# FOTA_MicroController.net
KiCad netlist of a schematic drawn in Altium Designer
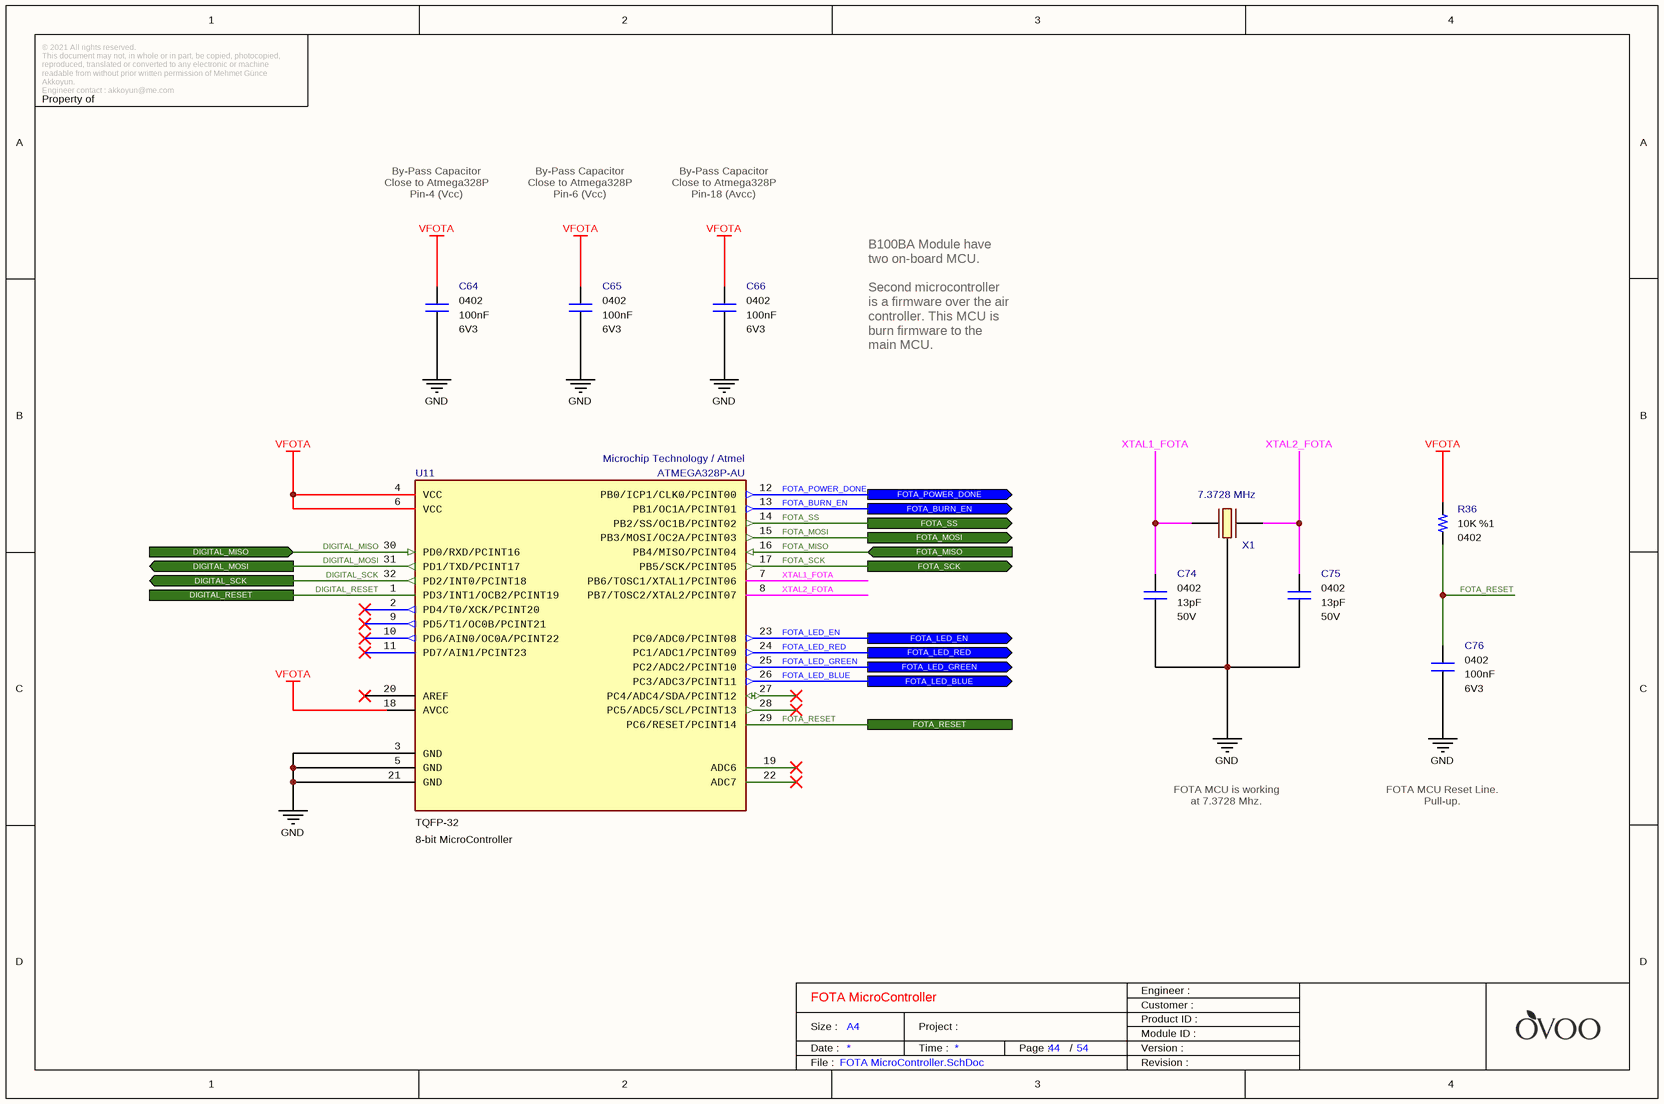
[diagram p0: FOTA MicroController.SchDoc]

(export (version "E")
  (design (tool "Eeschema 10.0.6"))
  (components
    (comp (ref "C64")
      (value "100nF")
      (footprint "CAPACITOR_0402")
      (description "Capacitor - 100nF [0402-6V3] (Ceramic)")
      (fields
        (field (name "TOLERANCE") "%10")
        (field (name "CASE") "0402")
        (field (name "VOLTAGE") "6V3")
        (field (name "MANUFACTURER PART NUMBER") "04026D104KAT4A")
      )
      (libsource (lib "Ovoo_Library") (part "Capacitor - 100nF [0402-6V3]"))
    )
    (comp (ref "C65")
      (value "100nF")
      (footprint "CAPACITOR_0402")
      (description "Capacitor - 100nF [0402-6V3] (Ceramic)")
      (fields
        (field (name "TOLERANCE") "%10")
        (field (name "CASE") "0402")
        (field (name "VOLTAGE") "6V3")
        (field (name "MANUFACTURER PART NUMBER") "04026D104KAT4A")
      )
      (libsource (lib "Ovoo_Library") (part "Capacitor - 100nF [0402-6V3]"))
    )
    (comp (ref "C66")
      (value "100nF")
      (footprint "CAPACITOR_0402")
      (description "Capacitor - 100nF [0402-6V3] (Ceramic)")
      (fields
        (field (name "TOLERANCE") "%10")
        (field (name "CASE") "0402")
        (field (name "VOLTAGE") "6V3")
        (field (name "MANUFACTURER PART NUMBER") "04026D104KAT4A")
      )
      (libsource (lib "Ovoo_Library") (part "Capacitor - 100nF [0402-6V3]"))
    )
    (comp (ref "C74")
      (value "13pF")
      (footprint "CAPACITOR_0402")
      (description "Capacitor - 13pF [0402] (Ceramic)")
      (fields
        (field (name "TOLERANCE") "1%")
        (field (name "VOLTAGE") "50V")
        (field (name "CASE") "0402")
        (field (name "MANUFACTURER PART NUMBER") "CBR04C130F5GAC")
      )
      (libsource (lib "Ovoo_Library") (part "Capacitor - 13pF [0402-50V]"))
    )
    (comp (ref "C75")
      (value "13pF")
      (footprint "CAPACITOR_0402")
      (description "Capacitor - 13pF [0402] (Ceramic)")
      (fields
        (field (name "TOLERANCE") "1%")
        (field (name "VOLTAGE") "50V")
        (field (name "CASE") "0402")
        (field (name "MANUFACTURER PART NUMBER") "CBR04C130F5GAC")
      )
      (libsource (lib "Ovoo_Library") (part "Capacitor - 13pF [0402-50V]"))
    )
    (comp (ref "C76")
      (value "100nF")
      (footprint "CAPACITOR_0402")
      (description "Capacitor - 100nF [0402-6V3] (Ceramic)")
      (fields
        (field (name "TOLERANCE") "%10")
        (field (name "CASE") "0402")
        (field (name "VOLTAGE") "6V3")
        (field (name "MANUFACTURER PART NUMBER") "04026D104KAT4A")
      )
      (libsource (lib "Ovoo_Library") (part "Capacitor - 100nF [0402-6V3]"))
    )
    (comp (ref "R36")
      (value "10K")
      (footprint "RESISTOR_0402")
      (description "Thick Film Resistors - SMD 1/16 W 10 Kohms 1%")
      (fields
        (field (name "TOLERANCE") "%1")
        (field (name "CASE") "0402")
        (field (name "MANUFACTURER PART NUMBER") "CRCW040210K0FKED")
        (field (name "MOUSER PART NUMBER") "71-CRCW0402-10K-E3")
      )
      (libsource (lib "Ovoo_Library") (part "Resistor - 10K"))
    )
    (comp (ref "U11")
      (value "8-bit MicroController")
      (footprint "TQFP32")
      (description "8-bit Microcontrollers - MCU 32KB In-system Flash 20MHz 1.8V-5.5V")
      (fields
        (field (name "CASE") "TQFP-32")
        (field (name "MOUSER PART NUMBER") "556-ATMEGA328P-AU")
        (field (name "MANUFACTURER PART NUMBER") "ATMEGA328P-AU")
        (field (name "MANUFACTURER NAME") "Microchip Technology / Atmel")
      )
      (libsource (lib "Ovoo_Library") (part "IC - ATMEGA328P"))
    )
    (comp (ref "X1")
      (value "7.3728 MHz")
      (footprint "ABRACON_CRYSTAL")
      (description "Crystals 7.3728MHz 18pF -40C +85C")
      (fields
        (field (name "TOLERANCE") "20 ppm")
        (field (name "MANUFACTURER PART NUMBER") "ABMM2-7.3728MHZ-E2-T")
      )
      (libsource (lib "Ovoo_Library") (part "Crystal - 7.3728 MHz (Abracon)"))
    )
  )
  (nets
    (net (code "1") (name "/DIGITAL_MISO") (class "Default")
      (node (ref "U11") (pin "30") (pinfunction "PD0/RXD/PCINT16_30") (pintype "input"))
    )
    (net (code "2") (name "/DIGITAL_MOSI") (class "Default")
      (node (ref "U11") (pin "31") (pinfunction "PD1/TXD/PCINT17_31") (pintype "output"))
    )
    (net (code "3") (name "/DIGITAL_RESET") (class "Default")
      (node (ref "U11") (pin "1") (pinfunction "PD3/INT1/OCB2/PCINT19_1") (pintype "passive"))
    )
    (net (code "4") (name "/DIGITAL_SCK") (class "Default")
      (node (ref "U11") (pin "32") (pinfunction "PD2/INT0/PCINT18_32") (pintype "output"))
    )
    (net (code "5") (name "/FOTA_BURN_EN") (class "Default")
      (node (ref "U11") (pin "13") (pinfunction "PB1/OC1A/PCINT01_13") (pintype "output"))
    )
    (net (code "6") (name "/FOTA_LED_BLUE") (class "Default")
      (node (ref "U11") (pin "26") (pinfunction "PC3/ADC3/PCINT11_26") (pintype "output"))
    )
    (net (code "7") (name "/FOTA_LED_EN") (class "Default")
      (node (ref "U11") (pin "23") (pinfunction "PC0/ADC0/PCINT08_23") (pintype "output"))
    )
    (net (code "8") (name "/FOTA_LED_GREEN") (class "Default")
      (node (ref "U11") (pin "25") (pinfunction "PC2/ADC2/PCINT10_25") (pintype "output"))
    )
    (net (code "9") (name "/FOTA_LED_RED") (class "Default")
      (node (ref "U11") (pin "24") (pinfunction "PC1/ADC1/PCINT09_24") (pintype "output"))
    )
    (net (code "10") (name "/FOTA_MISO") (class "Default")
      (node (ref "U11") (pin "16") (pinfunction "PB4/MISO/PCINT04_16") (pintype "input"))
    )
    (net (code "11") (name "/FOTA_MOSI") (class "Default")
      (node (ref "U11") (pin "15") (pinfunction "PB3/MOSI/OC2A/PCINT03_15") (pintype "output"))
    )
    (net (code "12") (name "/FOTA_POWER_DONE") (class "Default")
      (node (ref "U11") (pin "12") (pinfunction "PB0/ICP1/CLK0/PCINT00_12") (pintype "output"))
    )
    (net (code "13") (name "/FOTA_RESET") (class "Default")
      (node (ref "C76") (pin "2") (pinfunction "2_2") (pintype "passive"))
      (node (ref "R36") (pin "1") (pinfunction "1_1") (pintype "passive"))
      (node (ref "U11") (pin "29") (pinfunction "PC6/RESET/PCINT14_29") (pintype "passive"))
    )
    (net (code "14") (name "/FOTA_SCK") (class "Default")
      (node (ref "U11") (pin "17") (pinfunction "PB5/SCK/PCINT05_17") (pintype "output"))
    )
    (net (code "15") (name "/FOTA_SS") (class "Default")
      (node (ref "U11") (pin "14") (pinfunction "PB2/SS/OC1B/PCINT02_14") (pintype "output"))
    )
    (net (code "16") (name "/XTAL1_FOTA") (class "Default")
      (node (ref "C74") (pin "2") (pinfunction "2_2") (pintype "passive"))
      (node (ref "U11") (pin "7") (pinfunction "PB6/TOSC1/XTAL1/PCINT06_7") (pintype "passive"))
      (node (ref "X1") (pin "3") (pinfunction "OUT/IN_3") (pintype "passive"))
    )
    (net (code "17") (name "/XTAL2_FOTA") (class "Default")
      (node (ref "C75") (pin "2") (pinfunction "2_2") (pintype "passive"))
      (node (ref "U11") (pin "8") (pinfunction "PB7/TOSC2/XTAL2/PCINT07_8") (pintype "passive"))
      (node (ref "X1") (pin "1") (pinfunction "IN/OUT_1") (pintype "passive"))
    )
    (net (code "18") (name "GND") (class "Default")
      (node (ref "C64") (pin "1") (pinfunction "1_1") (pintype "passive"))
      (node (ref "C65") (pin "1") (pinfunction "1_1") (pintype "passive"))
      (node (ref "C66") (pin "1") (pinfunction "1_1") (pintype "passive"))
      (node (ref "C74") (pin "1") (pinfunction "1_1") (pintype "passive"))
      (node (ref "C75") (pin "1") (pinfunction "1_1") (pintype "passive"))
      (node (ref "C76") (pin "1") (pinfunction "1_1") (pintype "passive"))
      (node (ref "U11") (pin "21") (pinfunction "GND_21") (pintype "power_in"))
      (node (ref "U11") (pin "3") (pinfunction "GND_3") (pintype "power_in"))
      (node (ref "U11") (pin "5") (pinfunction "GND_5") (pintype "power_in"))
      (node (ref "X1") (pin "2") (pinfunction "GND_2") (pintype "passive"))
    )
    (net (code "19") (name "VFOTA") (class "Default")
      (node (ref "C64") (pin "2") (pinfunction "2_2") (pintype "passive"))
      (node (ref "C65") (pin "2") (pinfunction "2_2") (pintype "passive"))
      (node (ref "C66") (pin "2") (pinfunction "2_2") (pintype "passive"))
      (node (ref "R36") (pin "2") (pinfunction "2_2") (pintype "passive"))
      (node (ref "U11") (pin "18") (pinfunction "AVCC_18") (pintype "passive"))
      (node (ref "U11") (pin "4") (pinfunction "VCC_4") (pintype "power_in"))
      (node (ref "U11") (pin "6") (pinfunction "VCC_6") (pintype "power_in"))
    )
    (net (code "20") (name "unconnected-(U11-ADC6-Pad19)") (class "Default")
      (node (ref "U11") (pin "19") (pinfunction "ADC6_19") (pintype "passive+no_connect"))
    )
    (net (code "21") (name "unconnected-(U11-ADC7-Pad22)") (class "Default")
      (node (ref "U11") (pin "22") (pinfunction "ADC7_22") (pintype "passive+no_connect"))
    )
    (net (code "22") (name "unconnected-(U11-AREF-Pad20)") (class "Default")
      (node (ref "U11") (pin "20") (pinfunction "AREF_20") (pintype "passive+no_connect"))
    )
    (net (code "23") (name "unconnected-(U11-PC4{slash}ADC4{slash}SDA{slash}PCINT12-Pad27)") (class "Default")
      (node (ref "U11") (pin "27") (pinfunction "PC4/ADC4/SDA/PCINT12_27") (pintype "bidirectional+no_connect"))
    )
    (net (code "24") (name "unconnected-(U11-PC5{slash}ADC5{slash}SCL{slash}PCINT13-Pad28)") (class "Default")
      (node (ref "U11") (pin "28") (pinfunction "PC5/ADC5/SCL/PCINT13_28") (pintype "output+no_connect"))
    )
    (net (code "25") (name "unconnected-(U11-PD4{slash}T0{slash}XCK{slash}PCINT20-Pad2)") (class "Default")
      (node (ref "U11") (pin "2") (pinfunction "PD4/T0/XCK/PCINT20_2") (pintype "output+no_connect"))
    )
    (net (code "26") (name "unconnected-(U11-PD5{slash}T1{slash}OC0B{slash}PCINT21-Pad9)") (class "Default")
      (node (ref "U11") (pin "9") (pinfunction "PD5/T1/OC0B/PCINT21_9") (pintype "output+no_connect"))
    )
    (net (code "27") (name "unconnected-(U11-PD6{slash}AIN0{slash}OC0A{slash}PCINT22-Pad10)") (class "Default")
      (node (ref "U11") (pin "10") (pinfunction "PD6/AIN0/OC0A/PCINT22_10") (pintype "output+no_connect"))
    )
    (net (code "28") (name "unconnected-(U11-PD7{slash}AIN1{slash}PCINT23-Pad11)") (class "Default")
      (node (ref "U11") (pin "11") (pinfunction "PD7/AIN1/PCINT23_11") (pintype "passive+no_connect"))
    )
    (net (code "29") (name "unconnected-(X1-GND-Pad4)") (class "Default")
      (node (ref "X1") (pin "4") (pinfunction "GND_4") (pintype "passive"))
    )
  )
)
